# BC.net
KiCad netlist of a schematic drawn in Altium Designer
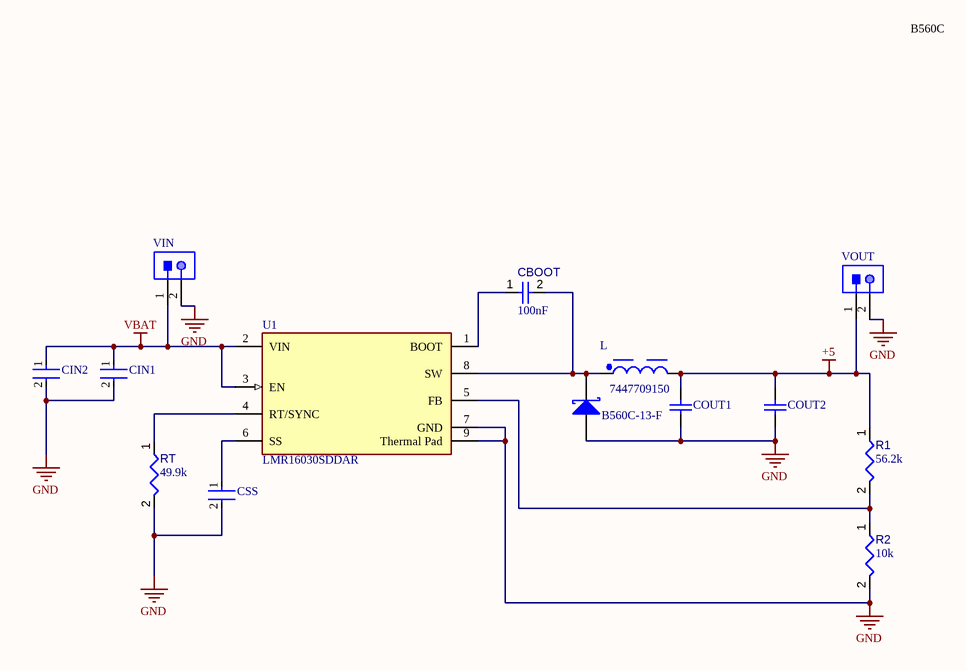
[diagram p0: BC.SchDoc]

(export (version "E")
  (design (tool "Eeschema 10.0.6"))
  (components
    (comp (ref "CBOOT")
      (value "100nF")
      (footprint "CAPC1608X90X40NL10T20")
      (description "Chip Capacitor, 100 nF, +/- 10%, 50 V, 0603 (1608 Metric)")
      (fields (field (name "TOLERANCE") "10%") (field (name "Comment") "Capacitor 100 nF +/-10% 50 V 0603"))
      (libsource (lib "Americas - McMaster University - McMaster Robosub") (part "CAP-NP-2"))
    )
    (comp (ref "CIN1")
      (value "GCJ32DC72A475ME01L")
      (footprint "FP-GCJ32D-0_4-MFG")
      (description "4.7uF ±20% 100V Ceramic Capacitor X7S 1210 (3225 Metric)")
      (libsource (lib "Altium Content Vault") (part "02cd4be3c70576c341d710602a673aa"))
    )
    (comp (ref "CIN2")
      (value "GCJ32DC72A475ME01L")
      (footprint "FP-GCJ32D-0_4-MFG")
      (description "4.7uF ±20% 100V Ceramic Capacitor X7S 1210 (3225 Metric)")
      (libsource (lib "Altium Content Vault") (part "02cd4be3c70576c341d710602a673aa"))
    )
    (comp (ref "COUT1")
      (value "GRM32ER61C476ME15L")
      (footprint "MURA-1210_H_2.7_M")
      (description "CAP, Ceramic, 47 uF, 20%, 16 V, 1210, RoHS, Tape and Reel")
      (fields (field (name "MANUFACTURER") "Murata") (field (name "TOLERANCE") "20%"))
      (libsource (lib "Altium Content Vault") (part "CAP-NP-2"))
    )
    (comp (ref "COUT2")
      (value "GRM32ER61C476ME15L")
      (footprint "MURA-1210_H_2.7_M")
      (description "CAP, Ceramic, 47 uF, 20%, 16 V, 1210, RoHS, Tape and Reel")
      (fields (field (name "MANUFACTURER") "Murata") (field (name "TOLERANCE") "20%"))
      (libsource (lib "Altium Content Vault") (part "CAP-NP-2"))
    )
    (comp (ref "CSS")
      (value "CC0603KRX7R9BB223")
      (footprint "FP-CC0603-DA-MFG")
      (description "CAP CER 0.022UF 50V X7R 0603")
      (fields (field (name "TOLERANCE") "10%") (field (name "VOLTAGE") "50V"))
      (libsource (lib "Altium Content Vault") (part "11868f565c42a9108669ba33697ecf6"))
    )
    (comp (ref "D")
      (value "B560C-13-F")
      (footprint "DIOD-B5X0C-2_M")
      (description "Schottky Barrier Rectifier, 5 A, 60 V, -55 to 125 degC, 2-Pin SMD, RoHS, Tape and Reel")
      (fields (field (name "MANUFACTURER") "DiodesIncorporated"))
      (libsource (lib "Altium Content Vault") (part "DSKY-KA-2"))
    )
    (comp (ref "L")
      (value "7447709150")
      (footprint "WE-PD_1210")
      (description "Power Choke Shielded Wirewound 15uH 20% 1KHz Ferrite 6.5A 26mOhm DCR T/R")
      (fields (field (name "TOLERANCE") "20%"))
      (libsource (lib "Altium Content Vault") (part "Inductor - 2"))
    )
    (comp (ref "R1")
      (value "56.2k")
      (footprint "RESC1608X55X25ML10T15")
      (description "Chip Resistor, 10 KOhm, +/- 1%, 01 W, -55 to 155 degC, 0603 (1608 Metric)")
      (fields (field (name "POWER") "100mW") (field (name "TOLERANCE") "1%"))
      (libsource (lib "Americas - McMaster University - McMaster Robosub") (part "RES-2"))
    )
    (comp (ref "R2")
      (value "10k")
      (footprint "RESC1608X55X25ML10T15")
      (description "Chip Resistor, 10 KOhm, +/- 1%, 01 W, -55 to 155 degC, 0603 (1608 Metric)")
      (fields (field (name "POWER") "100mW") (field (name "TOLERANCE") "1%"))
      (libsource (lib "Americas - McMaster University - McMaster Robosub") (part "RES-2"))
    )
    (comp (ref "RT")
      (value "49.9k")
      (footprint "RESC1608X55X25ML10T15")
      (description "Chip Resistor, 10 KOhm, +/- 1%, 01 W, -55 to 155 degC, 0603 (1608 Metric)")
      (fields (field (name "POWER") "100mW") (field (name "TOLERANCE") "1%"))
      (libsource (lib "Americas - McMaster University - McMaster Robosub") (part "RES-2"))
    )
    (comp (ref "U1")
      (value "LMR16030SDDAR")
      (footprint "FP-DDA0008E-IPC_A")
      (description "IC REG BUCK ADJUSTABLE 3A 8SOPWR")
      (libsource (lib "Altium Content Vault") (part "13dd98d11c1fbda804455ea10f69a88"))
    )
    (comp (ref "VIN")
      (value "S2B-PH-K-S(LF)(SN)")
      (footprint "JST-S2B-PH-K-S_V")
      (fields (field (name "MANUFACTURER") "Japan Solderless Terminals"))
      (libsource (lib "Americas - McMaster University - McMaster Robosub") (part "CN-1P-M-R2"))
    )
    (comp (ref "VOUT")
      (value "S2B-PH-K-S(LF)(SN)")
      (footprint "JST-S2B-PH-K-S_V")
      (fields (field (name "MANUFACTURER") "Japan Solderless Terminals"))
      (libsource (lib "Americas - McMaster University - McMaster Robosub") (part "CN-1P-M-R2"))
    )
  )
  (nets
    (net (code "1") (name "+5") (class "Default")
      (node (ref "COUT1") (pin "2") (pinfunction "2_2") (pintype "passive"))
      (node (ref "COUT2") (pin "2") (pinfunction "2_2") (pintype "passive"))
      (node (ref "L") (pin "2") (pinfunction "2_2") (pintype "passive"))
      (node (ref "R1") (pin "1") (pinfunction "1_1") (pintype "passive"))
      (node (ref "VOUT") (pin "1") (pinfunction "1_1") (pintype "passive"))
    )
    (net (code "2") (name "GND") (class "Default")
      (node (ref "CIN1") (pin "2") (pinfunction "2_2") (pintype "passive"))
      (node (ref "CIN2") (pin "2") (pinfunction "2_2") (pintype "passive"))
      (node (ref "COUT1") (pin "1") (pinfunction "1_1") (pintype "passive"))
      (node (ref "COUT2") (pin "1") (pinfunction "1_1") (pintype "passive"))
      (node (ref "CSS") (pin "2") (pinfunction "2_2") (pintype "passive"))
      (node (ref "D") (pin "2") (pinfunction "A_2") (pintype "passive"))
      (node (ref "R2") (pin "2") (pinfunction "2_2") (pintype "passive"))
      (node (ref "RT") (pin "2") (pinfunction "2_2") (pintype "passive"))
      (node (ref "U1") (pin "7") (pinfunction "GND_7") (pintype "power_in"))
      (node (ref "U1") (pin "9") (pinfunction "Thermal_Pad_9") (pintype "power_in"))
      (node (ref "VIN") (pin "2") (pinfunction "2_2") (pintype "passive"))
      (node (ref "VOUT") (pin "2") (pinfunction "2_2") (pintype "passive"))
    )
    (net (code "3") (name "Net-(D-K)") (class "Default")
      (node (ref "CBOOT") (pin "2") (pinfunction "2_2") (pintype "passive"))
      (node (ref "D") (pin "1") (pinfunction "K_1") (pintype "passive"))
      (node (ref "L") (pin "1") (pinfunction "1_1") (pintype "passive"))
      (node (ref "U1") (pin "8") (pinfunction "SW_8") (pintype "passive"))
    )
    (net (code "4") (name "Net-(U1-BOOT)") (class "Default")
      (node (ref "CBOOT") (pin "1") (pinfunction "1_1") (pintype "passive"))
      (node (ref "U1") (pin "1") (pinfunction "BOOT_1") (pintype "passive"))
    )
    (net (code "5") (name "Net-(U1-FB)") (class "Default")
      (node (ref "R1") (pin "2") (pinfunction "2_2") (pintype "passive"))
      (node (ref "R2") (pin "1") (pinfunction "1_1") (pintype "passive"))
      (node (ref "U1") (pin "5") (pinfunction "FB_5") (pintype "passive"))
    )
    (net (code "6") (name "Net-(U1-RT{slash}SYNC)") (class "Default")
      (node (ref "RT") (pin "1") (pinfunction "1_1") (pintype "passive"))
      (node (ref "U1") (pin "4") (pinfunction "RT/SYNC_4") (pintype "passive"))
    )
    (net (code "7") (name "Net-(U1-SS)") (class "Default")
      (node (ref "CSS") (pin "1") (pinfunction "1_1") (pintype "passive"))
      (node (ref "U1") (pin "6") (pinfunction "SS_6") (pintype "passive"))
    )
    (net (code "8") (name "VBAT") (class "Default")
      (node (ref "CIN1") (pin "1") (pinfunction "1_1") (pintype "passive"))
      (node (ref "CIN2") (pin "1") (pinfunction "1_1") (pintype "passive"))
      (node (ref "U1") (pin "2") (pinfunction "VIN_2") (pintype "power_in"))
      (node (ref "U1") (pin "3") (pinfunction "EN_3") (pintype "input"))
      (node (ref "VIN") (pin "1") (pinfunction "1_1") (pintype "passive"))
    )
  )
)
